# Sch_ALICE.net
KiCad netlist of a schematic drawn in Altium Designer
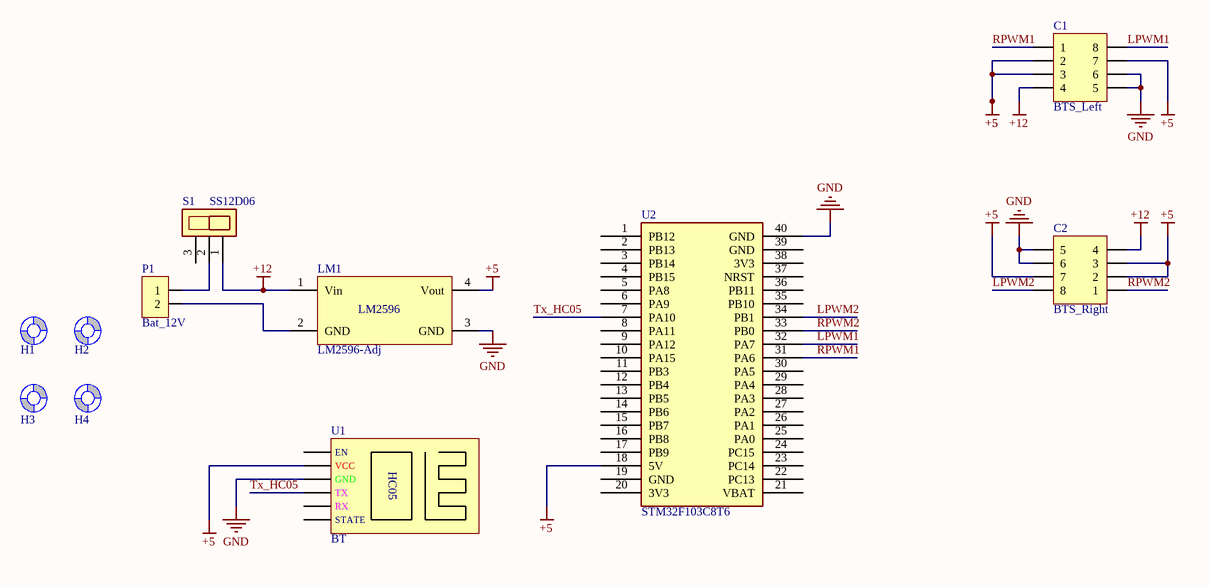
[diagram p0: Sch_ALICE.SchDoc]

(export (version "E")
  (design (tool "Eeschema 10.0.6"))
  (components
    (comp (ref "C1")
      (value "BTS_Left")
      (footprint "JP4-D2T")
      (description "WR-PHD 2.54 mm Dual Socket Header")
      (fields
        (field (name "MANUFACTURER") "Würth Elektronik eiSos GmbH")
        (field (name "PARTNO") "61300821821")
        (field (name "CREATED BY") "Karrer Zheng")
      )
      (libsource (lib "Altium Library") (part "JP4x2"))
    )
    (comp (ref "C2")
      (value "BTS_Right")
      (footprint "JP4-D2T")
      (description "WR-PHD 2.54 mm Dual Socket Header")
      (fields
        (field (name "MANUFACTURER") "Würth Elektronik eiSos GmbH")
        (field (name "PARTNO") "61300821821")
        (field (name "CREATED BY") "Karrer Zheng")
      )
      (libsource (lib "") (part "JP4x2_1"))
    )
    (comp (ref "H1")
      (value "Screw Hole")
      (footprint "SCREW/3.0/6.0")
      (libsource (lib "chipfc_libs") (part "Screw Hole"))
    )
    (comp (ref "H2")
      (value "Screw Hole")
      (footprint "SCREW/3.0/6.0")
      (libsource (lib "chipfc_libs") (part "Screw Hole"))
    )
    (comp (ref "H3")
      (value "Screw Hole")
      (footprint "SCREW/3.0/6.0")
      (libsource (lib "chipfc_libs") (part "Screw Hole"))
    )
    (comp (ref "H4")
      (value "Screw Hole")
      (footprint "SCREW/3.0/6.0")
      (libsource (lib "chipfc_libs") (part "Screw Hole"))
    )
    (comp (ref "LM1")
      (value "LM2596-Adj")
      (footprint "lm2596")
      (description "Designed By @Alixahedi")
      (libsource (lib "LM2596-Adj") (part "LM2596-Adj"))
    )
    (comp (ref "P1")
      (value "Bat_12V")
      (footprint "HDR/Terminal/2/5mm")
      (description "Header, 2-Pin")
      (libsource (lib "connectors") (part "Header 2"))
    )
    (comp (ref "S1")
      (value "SS12D06")
      (footprint "SS12D06")
      (description "Lying Slide Switch 3 Pins.")
      (libsource (lib "Buttons & Switches") (part "SS12D06"))
    )
    (comp (ref "U1")
      (value "BT")
      (footprint "HC05")
      (description "Bluetooth HC05 Module")
      (libsource (lib "Schlib1") (part "HC05"))
    )
    (comp (ref "U2")
      (value "STM32F103C8T6")
      (footprint "Stm32 BluePill")
      (description "Designed By @Alixahedi")
      (libsource (lib "Stm32 Blue Pill") (part "BluePill"))
    )
  )
  (nets
    (net (code "1") (name "+5") (class "Default")
      (node (ref "C1") (pin "2") (pinfunction "2_2") (pintype "passive"))
      (node (ref "C1") (pin "3") (pinfunction "3_3") (pintype "passive"))
      (node (ref "C1") (pin "7") (pinfunction "7_7") (pintype "passive"))
      (node (ref "C2") (pin "2") (pinfunction "2_2") (pintype "passive"))
      (node (ref "C2") (pin "3") (pinfunction "3_3") (pintype "passive"))
      (node (ref "C2") (pin "7") (pinfunction "7_7") (pintype "passive"))
      (node (ref "LM1") (pin "4") (pinfunction "Vout_4") (pintype "passive"))
      (node (ref "U1") (pin "2") (pintype "passive"))
      (node (ref "U2") (pin "18") (pinfunction "5V_18") (pintype "passive"))
    )
    (net (code "2") (name "+12") (class "Default")
      (node (ref "C1") (pin "4") (pinfunction "4_4") (pintype "passive"))
      (node (ref "C2") (pin "4") (pinfunction "4_4") (pintype "passive"))
      (node (ref "LM1") (pin "1") (pinfunction "Vin_1") (pintype "passive"))
      (node (ref "S1") (pin "1") (pintype "passive"))
    )
    (net (code "3") (name "/LPWM1") (class "Default")
      (node (ref "C1") (pin "8") (pinfunction "8_8") (pintype "passive"))
      (node (ref "U2") (pin "32") (pinfunction "PA7_32") (pintype "passive"))
    )
    (net (code "4") (name "/LPWM2") (class "Default")
      (node (ref "C2") (pin "8") (pinfunction "8_8") (pintype "passive"))
      (node (ref "U2") (pin "34") (pinfunction "PB1_34") (pintype "passive"))
    )
    (net (code "5") (name "/RPWM1") (class "Default")
      (node (ref "C1") (pin "1") (pinfunction "1_1") (pintype "passive"))
      (node (ref "U2") (pin "31") (pinfunction "PA6_31") (pintype "passive"))
    )
    (net (code "6") (name "/RPWM2") (class "Default")
      (node (ref "C2") (pin "1") (pinfunction "1_1") (pintype "passive"))
      (node (ref "U2") (pin "33") (pinfunction "PB0_33") (pintype "passive"))
    )
    (net (code "7") (name "/Tx_HC05") (class "Default")
      (node (ref "U1") (pin "4") (pintype "passive"))
      (node (ref "U2") (pin "7") (pinfunction "PA10_7") (pintype "passive"))
    )
    (net (code "8") (name "GND") (class "Default")
      (node (ref "C1") (pin "5") (pinfunction "5_5") (pintype "passive"))
      (node (ref "C1") (pin "6") (pinfunction "6_6") (pintype "passive"))
      (node (ref "C2") (pin "5") (pinfunction "5_5") (pintype "passive"))
      (node (ref "C2") (pin "6") (pinfunction "6_6") (pintype "passive"))
      (node (ref "LM1") (pin "3") (pinfunction "GND_3") (pintype "passive"))
      (node (ref "U1") (pin "3") (pintype "passive"))
      (node (ref "U2") (pin "40") (pinfunction "GND_40") (pintype "passive"))
    )
    (net (code "9") (name "Net-(LM1-GND-Pad2)") (class "Default")
      (node (ref "LM1") (pin "2") (pinfunction "GND_2") (pintype "passive"))
      (node (ref "P1") (pin "2") (pinfunction "2_2") (pintype "passive"))
    )
    (net (code "10") (name "Net-(P1-Pad1)") (class "Default")
      (node (ref "P1") (pin "1") (pinfunction "1_1") (pintype "passive"))
      (node (ref "S1") (pin "2") (pintype "passive"))
    )
    (net (code "11") (name "unconnected-(H1-Screw-Pad1)") (class "Default")
      (node (ref "H1") (pin "1") (pinfunction "Screw_1") (pintype "passive"))
    )
    (net (code "12") (name "unconnected-(H2-Screw-Pad1)") (class "Default")
      (node (ref "H2") (pin "1") (pinfunction "Screw_1") (pintype "passive"))
    )
    (net (code "13") (name "unconnected-(H3-Screw-Pad1)") (class "Default")
      (node (ref "H3") (pin "1") (pinfunction "Screw_1") (pintype "passive"))
    )
    (net (code "14") (name "unconnected-(H4-Screw-Pad1)") (class "Default")
      (node (ref "H4") (pin "1") (pinfunction "Screw_1") (pintype "passive"))
    )
    (net (code "15") (name "unconnected-(S1-Pad3)") (class "Default")
      (node (ref "S1") (pin "3") (pintype "passive"))
    )
    (net (code "16") (name "unconnected-(U1-Pad1)") (class "Default")
      (node (ref "U1") (pin "1") (pintype "passive"))
    )
    (net (code "17") (name "unconnected-(U1-Pad5)") (class "Default")
      (node (ref "U1") (pin "5") (pintype "passive"))
    )
    (net (code "18") (name "unconnected-(U1-Pad6)") (class "Default")
      (node (ref "U1") (pin "6") (pintype "passive"))
    )
    (net (code "19") (name "unconnected-(U2-3V3-Pad20)") (class "Default")
      (node (ref "U2") (pin "20") (pinfunction "3V3_20") (pintype "passive"))
    )
    (net (code "20") (name "unconnected-(U2-3V3-Pad38)") (class "Default")
      (node (ref "U2") (pin "38") (pinfunction "3V3_38") (pintype "passive"))
    )
    (net (code "21") (name "unconnected-(U2-GND-Pad19)") (class "Default")
      (node (ref "U2") (pin "19") (pinfunction "GND_19") (pintype "passive"))
    )
    (net (code "22") (name "unconnected-(U2-GND-Pad39)") (class "Default")
      (node (ref "U2") (pin "39") (pinfunction "GND_39") (pintype "passive"))
    )
    (net (code "23") (name "unconnected-(U2-NRST-Pad37)") (class "Default")
      (node (ref "U2") (pin "37") (pinfunction "NRST_37") (pintype "passive"))
    )
    (net (code "24") (name "unconnected-(U2-PA0-Pad25)") (class "Default")
      (node (ref "U2") (pin "25") (pinfunction "PA0_25") (pintype "passive"))
    )
    (net (code "25") (name "unconnected-(U2-PA1-Pad26)") (class "Default")
      (node (ref "U2") (pin "26") (pinfunction "PA1_26") (pintype "passive"))
    )
    (net (code "26") (name "unconnected-(U2-PA2-Pad27)") (class "Default")
      (node (ref "U2") (pin "27") (pinfunction "PA2_27") (pintype "passive"))
    )
    (net (code "27") (name "unconnected-(U2-PA3-Pad28)") (class "Default")
      (node (ref "U2") (pin "28") (pinfunction "PA3_28") (pintype "passive"))
    )
    (net (code "28") (name "unconnected-(U2-PA4-Pad29)") (class "Default")
      (node (ref "U2") (pin "29") (pinfunction "PA4_29") (pintype "passive"))
    )
    (net (code "29") (name "unconnected-(U2-PA5-Pad30)") (class "Default")
      (node (ref "U2") (pin "30") (pinfunction "PA5_30") (pintype "passive"))
    )
    (net (code "30") (name "unconnected-(U2-PA8-Pad5)") (class "Default")
      (node (ref "U2") (pin "5") (pinfunction "PA8_5") (pintype "passive"))
    )
    (net (code "31") (name "unconnected-(U2-PA9-Pad6)") (class "Default")
      (node (ref "U2") (pin "6") (pinfunction "PA9_6") (pintype "passive"))
    )
    (net (code "32") (name "unconnected-(U2-PA11-Pad8)") (class "Default")
      (node (ref "U2") (pin "8") (pinfunction "PA11_8") (pintype "passive"))
    )
    (net (code "33") (name "unconnected-(U2-PA12-Pad9)") (class "Default")
      (node (ref "U2") (pin "9") (pinfunction "PA12_9") (pintype "passive"))
    )
    (net (code "34") (name "unconnected-(U2-PA15-Pad10)") (class "Default")
      (node (ref "U2") (pin "10") (pinfunction "PA15_10") (pintype "passive"))
    )
    (net (code "35") (name "unconnected-(U2-PB3-Pad11)") (class "Default")
      (node (ref "U2") (pin "11") (pinfunction "PB3_11") (pintype "passive"))
    )
    (net (code "36") (name "unconnected-(U2-PB4-Pad12)") (class "Default")
      (node (ref "U2") (pin "12") (pinfunction "PB4_12") (pintype "passive"))
    )
    (net (code "37") (name "unconnected-(U2-PB5-Pad13)") (class "Default")
      (node (ref "U2") (pin "13") (pinfunction "PB5_13") (pintype "passive"))
    )
    (net (code "38") (name "unconnected-(U2-PB6-Pad14)") (class "Default")
      (node (ref "U2") (pin "14") (pinfunction "PB6_14") (pintype "passive"))
    )
    (net (code "39") (name "unconnected-(U2-PB7-Pad15)") (class "Default")
      (node (ref "U2") (pin "15") (pinfunction "PB7_15") (pintype "passive"))
    )
    (net (code "40") (name "unconnected-(U2-PB8-Pad16)") (class "Default")
      (node (ref "U2") (pin "16") (pinfunction "PB8_16") (pintype "passive"))
    )
    (net (code "41") (name "unconnected-(U2-PB9-Pad17)") (class "Default")
      (node (ref "U2") (pin "17") (pinfunction "PB9_17") (pintype "passive"))
    )
    (net (code "42") (name "unconnected-(U2-PB10-Pad35)") (class "Default")
      (node (ref "U2") (pin "35") (pinfunction "PB10_35") (pintype "passive"))
    )
    (net (code "43") (name "unconnected-(U2-PB11-Pad36)") (class "Default")
      (node (ref "U2") (pin "36") (pinfunction "PB11_36") (pintype "passive"))
    )
    (net (code "44") (name "unconnected-(U2-PB12-Pad1)") (class "Default")
      (node (ref "U2") (pin "1") (pinfunction "PB12_1") (pintype "passive"))
    )
    (net (code "45") (name "unconnected-(U2-PB13-Pad2)") (class "Default")
      (node (ref "U2") (pin "2") (pinfunction "PB13_2") (pintype "passive"))
    )
    (net (code "46") (name "unconnected-(U2-PB14-Pad3)") (class "Default")
      (node (ref "U2") (pin "3") (pinfunction "PB14_3") (pintype "passive"))
    )
    (net (code "47") (name "unconnected-(U2-PB15-Pad4)") (class "Default")
      (node (ref "U2") (pin "4") (pinfunction "PB15_4") (pintype "passive"))
    )
    (net (code "48") (name "unconnected-(U2-PC13-Pad22)") (class "Default")
      (node (ref "U2") (pin "22") (pinfunction "PC13_22") (pintype "passive"))
    )
    (net (code "49") (name "unconnected-(U2-PC14-Pad23)") (class "Default")
      (node (ref "U2") (pin "23") (pinfunction "PC14_23") (pintype "passive"))
    )
    (net (code "50") (name "unconnected-(U2-PC15-Pad24)") (class "Default")
      (node (ref "U2") (pin "24") (pinfunction "PC15_24") (pintype "passive"))
    )
    (net (code "51") (name "unconnected-(U2-VBAT-Pad21)") (class "Default")
      (node (ref "U2") (pin "21") (pinfunction "VBAT_21") (pintype "passive"))
    )
  )
)
